# IR_sensor.net
KiCad netlist of a schematic drawn in EAGLE
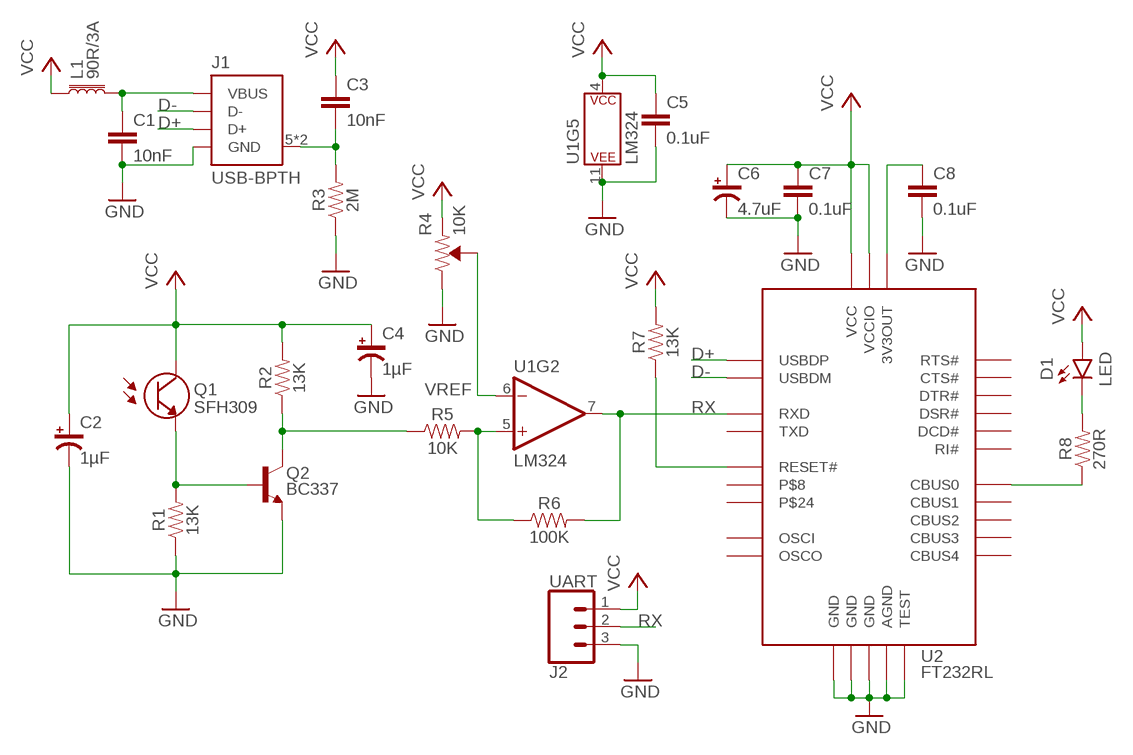
[diagram p0: schematic, sheet 1]

(export (version "E")
  (design (tool "Eeschema 10.0.6"))
  (components
    (comp (ref "C1")
      (value "10nF")
      (footprint "eagle-import:CAP-PTH-2.5MM")
      (libsource (lib "eagle-import") (part "CAPPTH2.5MM"))
    )
    (comp (ref "C2")
      (value "1µF")
      (footprint "eagle-import:CPOL-RADIAL-2.5MM-5MM")
      (libsource (lib "eagle-import") (part "CAP-POL"))
    )
    (comp (ref "C3")
      (value "10nF")
      (footprint "eagle-import:CAP-PTH-5MM")
      (libsource (lib "eagle-import") (part "CAPPTH-5MM"))
    )
    (comp (ref "C4")
      (value "1µF")
      (footprint "eagle-import:CPOL-RADIAL-2.5MM-5MM")
      (libsource (lib "eagle-import") (part "CAP-POL"))
    )
    (comp (ref "C5")
      (value "0.1uF")
      (footprint "eagle-import:CAP-PTH-5MM")
      (libsource (lib "eagle-import") (part "CAPPTH-5MM"))
    )
    (comp (ref "C6")
      (value "4.7uF")
      (footprint "eagle-import:CPOL-RADIAL-2.5MM-5MM")
      (libsource (lib "eagle-import") (part "CAP-POL"))
    )
    (comp (ref "C7")
      (value "0.1uF")
      (footprint "eagle-import:CAP-PTH-5MM")
      (libsource (lib "eagle-import") (part "CAPPTH-5MM"))
    )
    (comp (ref "C8")
      (value "0.1uF")
      (footprint "eagle-import:CAP-PTH-5MM")
      (libsource (lib "eagle-import") (part "CAPPTH-5MM"))
    )
    (comp (ref "D1")
      (value "LED")
      (footprint "eagle-import:LED_5MM")
      (libsource (lib "eagle-import") (part "LEDPTH-5MM"))
    )
    (comp (ref "J1")
      (value "USB-BPTH")
      (footprint "eagle-import:USB-B-PTH")
      (libsource (lib "eagle-import") (part "USB-BPTH"))
    )
    (comp (ref "J2")
      (value "UART")
      (footprint "eagle-import:1X03")
      (libsource (lib "eagle-import") (part "CONN_03"))
    )
    (comp (ref "L1")
      (value "90R/3A")
      (footprint "eagle-import:AXIAL-0.3")
      (libsource (lib "eagle-import") (part "FERRITE_BEADPTH"))
    )
    (comp (ref "Q1")
      (value "SFH309")
      (footprint "eagle-import:LED_3MM_R")
      (libsource (lib "eagle-import") (part "PHOTOTRANSISTORPTH-R"))
    )
    (comp (ref "Q2")
      (value "BC337")
      (footprint "eagle-import:TO-92")
      (libsource (lib "eagle-import") (part "NPNPTH"))
    )
    (comp (ref "R1")
      (value "13K")
      (footprint "eagle-import:AXIAL-0.3")
      (libsource (lib "eagle-import") (part "RESISTORPTH"))
    )
    (comp (ref "R2")
      (value "13K")
      (footprint "eagle-import:AXIAL-0.3")
      (libsource (lib "eagle-import") (part "RESISTORPTH"))
    )
    (comp (ref "R3")
      (value "2M")
      (footprint "eagle-import:AXIAL-0.3")
      (libsource (lib "eagle-import") (part "RESISTORPTH"))
    )
    (comp (ref "R4")
      (value "10K")
      (footprint "eagle-import:TRIMPOT")
      (libsource (lib "eagle-import") (part "TRIMPOT"))
    )
    (comp (ref "R5")
      (value "10K")
      (footprint "eagle-import:AXIAL-0.3")
      (libsource (lib "eagle-import") (part "RESISTORPTH"))
    )
    (comp (ref "R6")
      (value "100K")
      (footprint "eagle-import:AXIAL-0.3")
      (libsource (lib "eagle-import") (part "RESISTORPTH"))
    )
    (comp (ref "R7")
      (value "13K")
      (footprint "eagle-import:AXIAL-0.3")
      (libsource (lib "eagle-import") (part "RESISTORPTH"))
    )
    (comp (ref "R8")
      (value "270R")
      (footprint "eagle-import:AXIAL-0.3")
      (libsource (lib "eagle-import") (part "RESISTORPTH"))
    )
    (comp (ref "U1")
      (value "LM324")
      (footprint "eagle-import:DIP14")
      (libsource (lib "eagle-import") (part "OP_AMP"))
    )
    (comp (ref "U2")
      (value "FT232RL")
      (footprint "eagle-import:TSSOP-28-BL")
      (libsource (lib "eagle-import") (part "FT232RL"))
    )
  )
  (nets
    (net (code "1") (name "/D+") (class "Default")
      (node (ref "J1") (pin "3") (pinfunction "D+_3") (pintype "bidirectional"))
      (node (ref "U2") (pin "15") (pinfunction "USBDP_15") (pintype "bidirectional"))
    )
    (net (code "2") (name "/D-") (class "Default")
      (node (ref "J1") (pin "2") (pinfunction "D-_2") (pintype "bidirectional"))
      (node (ref "U2") (pin "16") (pinfunction "USBDM_16") (pintype "bidirectional"))
    )
    (net (code "3") (name "/RX") (class "Default")
      (node (ref "J2") (pin "2") (pinfunction "2_2") (pintype "passive"))
      (node (ref "R6") (pin "P$2") (pinfunction "2_P$2") (pintype "passive"))
      (node (ref "U1") (pin "7") (pinfunction "OUT_7") (pintype "output"))
      (node (ref "U2") (pin "5") (pinfunction "RXD_5") (pintype "input"))
    )
    (net (code "4") (name "/VREF") (class "Default")
      (node (ref "R4") (pin "P$3") (pinfunction "WIPER_P$3") (pintype "passive"))
      (node (ref "U1") (pin "6") (pinfunction "-IN_6") (pintype "input"))
    )
    (net (code "5") (name "GND") (class "Default")
      (node (ref "C1") (pin "2") (pinfunction "2_2") (pintype "passive"))
      (node (ref "C2") (pin "2") (pinfunction "-_2") (pintype "passive"))
      (node (ref "C4") (pin "2") (pinfunction "-_2") (pintype "passive"))
      (node (ref "C5") (pin "2") (pinfunction "2_2") (pintype "passive"))
      (node (ref "C6") (pin "2") (pinfunction "-_2") (pintype "passive"))
      (node (ref "C7") (pin "2") (pinfunction "2_2") (pintype "passive"))
      (node (ref "C8") (pin "2") (pinfunction "2_2") (pintype "passive"))
      (node (ref "J1") (pin "4") (pinfunction "GND_4") (pintype "power_in"))
      (node (ref "J2") (pin "3") (pinfunction "3_3") (pintype "passive"))
      (node (ref "Q2") (pin "1") (pinfunction "E_1") (pintype "passive"))
      (node (ref "R1") (pin "P$1") (pinfunction "1_P$1") (pintype "passive"))
      (node (ref "R3") (pin "P$1") (pinfunction "1_P$1") (pintype "passive"))
      (node (ref "R4") (pin "P$2") (pinfunction "CW_P$2") (pintype "passive"))
      (node (ref "U1") (pin "11") (pinfunction "P$V-_11") (pintype "power_in"))
      (node (ref "U2") (pin "18") (pinfunction "GND_18") (pintype "power_in"))
      (node (ref "U2") (pin "21") (pinfunction "GND_21") (pintype "power_in"))
      (node (ref "U2") (pin "25") (pinfunction "AGND_25") (pintype "power_in"))
      (node (ref "U2") (pin "26") (pinfunction "TEST_26") (pintype "input"))
      (node (ref "U2") (pin "7") (pinfunction "GND_7") (pintype "power_in"))
    )
    (net (code "6") (name "Net-(J1-VBUS)") (class "Default")
      (node (ref "C1") (pin "1") (pinfunction "1_1") (pintype "passive"))
      (node (ref "J1") (pin "1") (pinfunction "VBUS_1") (pintype "power_in"))
      (node (ref "L1") (pin "P$2") (pinfunction "2_P$2") (pintype "passive"))
    )
    (net (code "7") (name "Net-(Q1-E)") (class "Default")
      (node (ref "Q1") (pin "A") (pinfunction "E_A") (pintype "passive"))
      (node (ref "Q2") (pin "2") (pinfunction "B_2") (pintype "passive"))
      (node (ref "R1") (pin "P$2") (pinfunction "2_P$2") (pintype "passive"))
    )
    (net (code "8") (name "Net-(Q2-C)") (class "Default")
      (node (ref "Q2") (pin "3") (pinfunction "C_3") (pintype "passive"))
      (node (ref "R2") (pin "P$1") (pinfunction "1_P$1") (pintype "passive"))
      (node (ref "R5") (pin "P$1") (pinfunction "1_P$1") (pintype "passive"))
    )
    (net (code "9") (name "Net-(R3-2)") (class "Default")
      (node (ref "C3") (pin "2") (pinfunction "2_2") (pintype "passive"))
      (node (ref "J1") (pin "5") (pinfunction "SHIELD_5") (pintype "passive"))
      (node (ref "J1") (pin "6") (pinfunction "SHIELD_6") (pintype "passive"))
      (node (ref "R3") (pin "P$2") (pinfunction "2_P$2") (pintype "passive"))
    )
    (net (code "10") (name "Net-(R5-2)") (class "Default")
      (node (ref "R5") (pin "P$2") (pinfunction "2_P$2") (pintype "passive"))
      (node (ref "R6") (pin "P$1") (pinfunction "1_P$1") (pintype "passive"))
      (node (ref "U1") (pin "5") (pinfunction "+IN_5") (pintype "input"))
    )
    (net (code "11") (name "Net-(R7-1)") (class "Default")
      (node (ref "R7") (pin "P$1") (pinfunction "1_P$1") (pintype "passive"))
      (node (ref "U2") (pin "19") (pinfunction "RESET#_19") (pintype "input"))
    )
    (net (code "12") (name "Net-(R8-1)") (class "Default")
      (node (ref "R8") (pin "P$1") (pinfunction "1_P$1") (pintype "passive"))
      (node (ref "U2") (pin "23") (pinfunction "CBUS0_23") (pintype "bidirectional"))
    )
    (net (code "13") (name "Net-(R8-2)") (class "Default")
      (node (ref "D1") (pin "K") (pinfunction "K_K") (pintype "passive"))
      (node (ref "R8") (pin "P$2") (pinfunction "2_P$2") (pintype "passive"))
    )
    (net (code "14") (name "Net-(U2-3V3OUT)") (class "Default")
      (node (ref "C8") (pin "1") (pinfunction "1_1") (pintype "passive"))
      (node (ref "U2") (pin "17") (pinfunction "3V3OUT_17") (pintype "output"))
    )
    (net (code "15") (name "VCC") (class "Default")
      (node (ref "C2") (pin "1") (pinfunction "+_1") (pintype "passive"))
      (node (ref "C3") (pin "1") (pinfunction "1_1") (pintype "passive"))
      (node (ref "C4") (pin "1") (pinfunction "+_1") (pintype "passive"))
      (node (ref "C5") (pin "1") (pinfunction "1_1") (pintype "passive"))
      (node (ref "C6") (pin "1") (pinfunction "+_1") (pintype "passive"))
      (node (ref "C7") (pin "1") (pinfunction "1_1") (pintype "passive"))
      (node (ref "D1") (pin "A") (pinfunction "A_A") (pintype "passive"))
      (node (ref "J2") (pin "1") (pinfunction "1_1") (pintype "passive"))
      (node (ref "L1") (pin "P$1") (pinfunction "1_P$1") (pintype "passive"))
      (node (ref "Q1") (pin "K") (pinfunction "C_K") (pintype "passive"))
      (node (ref "R2") (pin "P$2") (pinfunction "2_P$2") (pintype "passive"))
      (node (ref "R4") (pin "P$1") (pinfunction "CCW_P$1") (pintype "passive"))
      (node (ref "R7") (pin "P$2") (pinfunction "2_P$2") (pintype "passive"))
      (node (ref "U1") (pin "4") (pinfunction "P$V+_4") (pintype "power_in"))
      (node (ref "U2") (pin "20") (pinfunction "VCC_20") (pintype "power_in"))
      (node (ref "U2") (pin "4") (pinfunction "VCCIO_4") (pintype "power_in"))
    )
    (net (code "16") (name "unconnected-(U2-CBUS1-Pad22)") (class "Default")
      (node (ref "U2") (pin "22") (pinfunction "CBUS1_22") (pintype "bidirectional"))
    )
    (net (code "17") (name "unconnected-(U2-CBUS2-Pad13)") (class "Default")
      (node (ref "U2") (pin "13") (pinfunction "CBUS2_13") (pintype "bidirectional"))
    )
    (net (code "18") (name "unconnected-(U2-CBUS3-Pad14)") (class "Default")
      (node (ref "U2") (pin "14") (pinfunction "CBUS3_14") (pintype "bidirectional"))
    )
    (net (code "19") (name "unconnected-(U2-CBUS4-Pad12)") (class "Default")
      (node (ref "U2") (pin "12") (pinfunction "CBUS4_12") (pintype "bidirectional"))
    )
    (net (code "20") (name "unconnected-(U2-CTS#-Pad11)") (class "Default")
      (node (ref "U2") (pin "11") (pinfunction "CTS#_11") (pintype "input"))
    )
    (net (code "21") (name "unconnected-(U2-DCD#-Pad10)") (class "Default")
      (node (ref "U2") (pin "10") (pinfunction "DCD#_10") (pintype "input"))
    )
    (net (code "22") (name "unconnected-(U2-DSR#-Pad9)") (class "Default")
      (node (ref "U2") (pin "9") (pinfunction "DSR#_9") (pintype "input"))
    )
    (net (code "23") (name "unconnected-(U2-DTR#-Pad2)") (class "Default")
      (node (ref "U2") (pin "2") (pinfunction "DTR#_2") (pintype "output"))
    )
    (net (code "24") (name "unconnected-(U2-OSCI-Pad27)") (class "Default")
      (node (ref "U2") (pin "27") (pinfunction "OSCI_27") (pintype "input"))
    )
    (net (code "25") (name "unconnected-(U2-OSCO-Pad28)") (class "Default")
      (node (ref "U2") (pin "28") (pinfunction "OSCO_28") (pintype "output"))
    )
    (net (code "26") (name "unconnected-(U2-P$8-Pad8)") (class "Default")
      (node (ref "U2") (pin "8") (pinfunction "P$8_8") (pintype "no_connect"))
    )
    (net (code "27") (name "unconnected-(U2-P$24-Pad24)") (class "Default")
      (node (ref "U2") (pin "24") (pinfunction "P$24_24") (pintype "no_connect"))
    )
    (net (code "28") (name "unconnected-(U2-RI#-Pad6)") (class "Default")
      (node (ref "U2") (pin "6") (pinfunction "RI#_6") (pintype "input"))
    )
    (net (code "29") (name "unconnected-(U2-RTS#-Pad3)") (class "Default")
      (node (ref "U2") (pin "3") (pinfunction "RTS#_3") (pintype "output"))
    )
    (net (code "30") (name "unconnected-(U2-TXD-Pad1)") (class "Default")
      (node (ref "U2") (pin "1") (pinfunction "TXD_1") (pintype "output"))
    )
  )
)
